# RF1_12V_RGBFlood.net
KiCad netlist of a schematic drawn in EAGLE
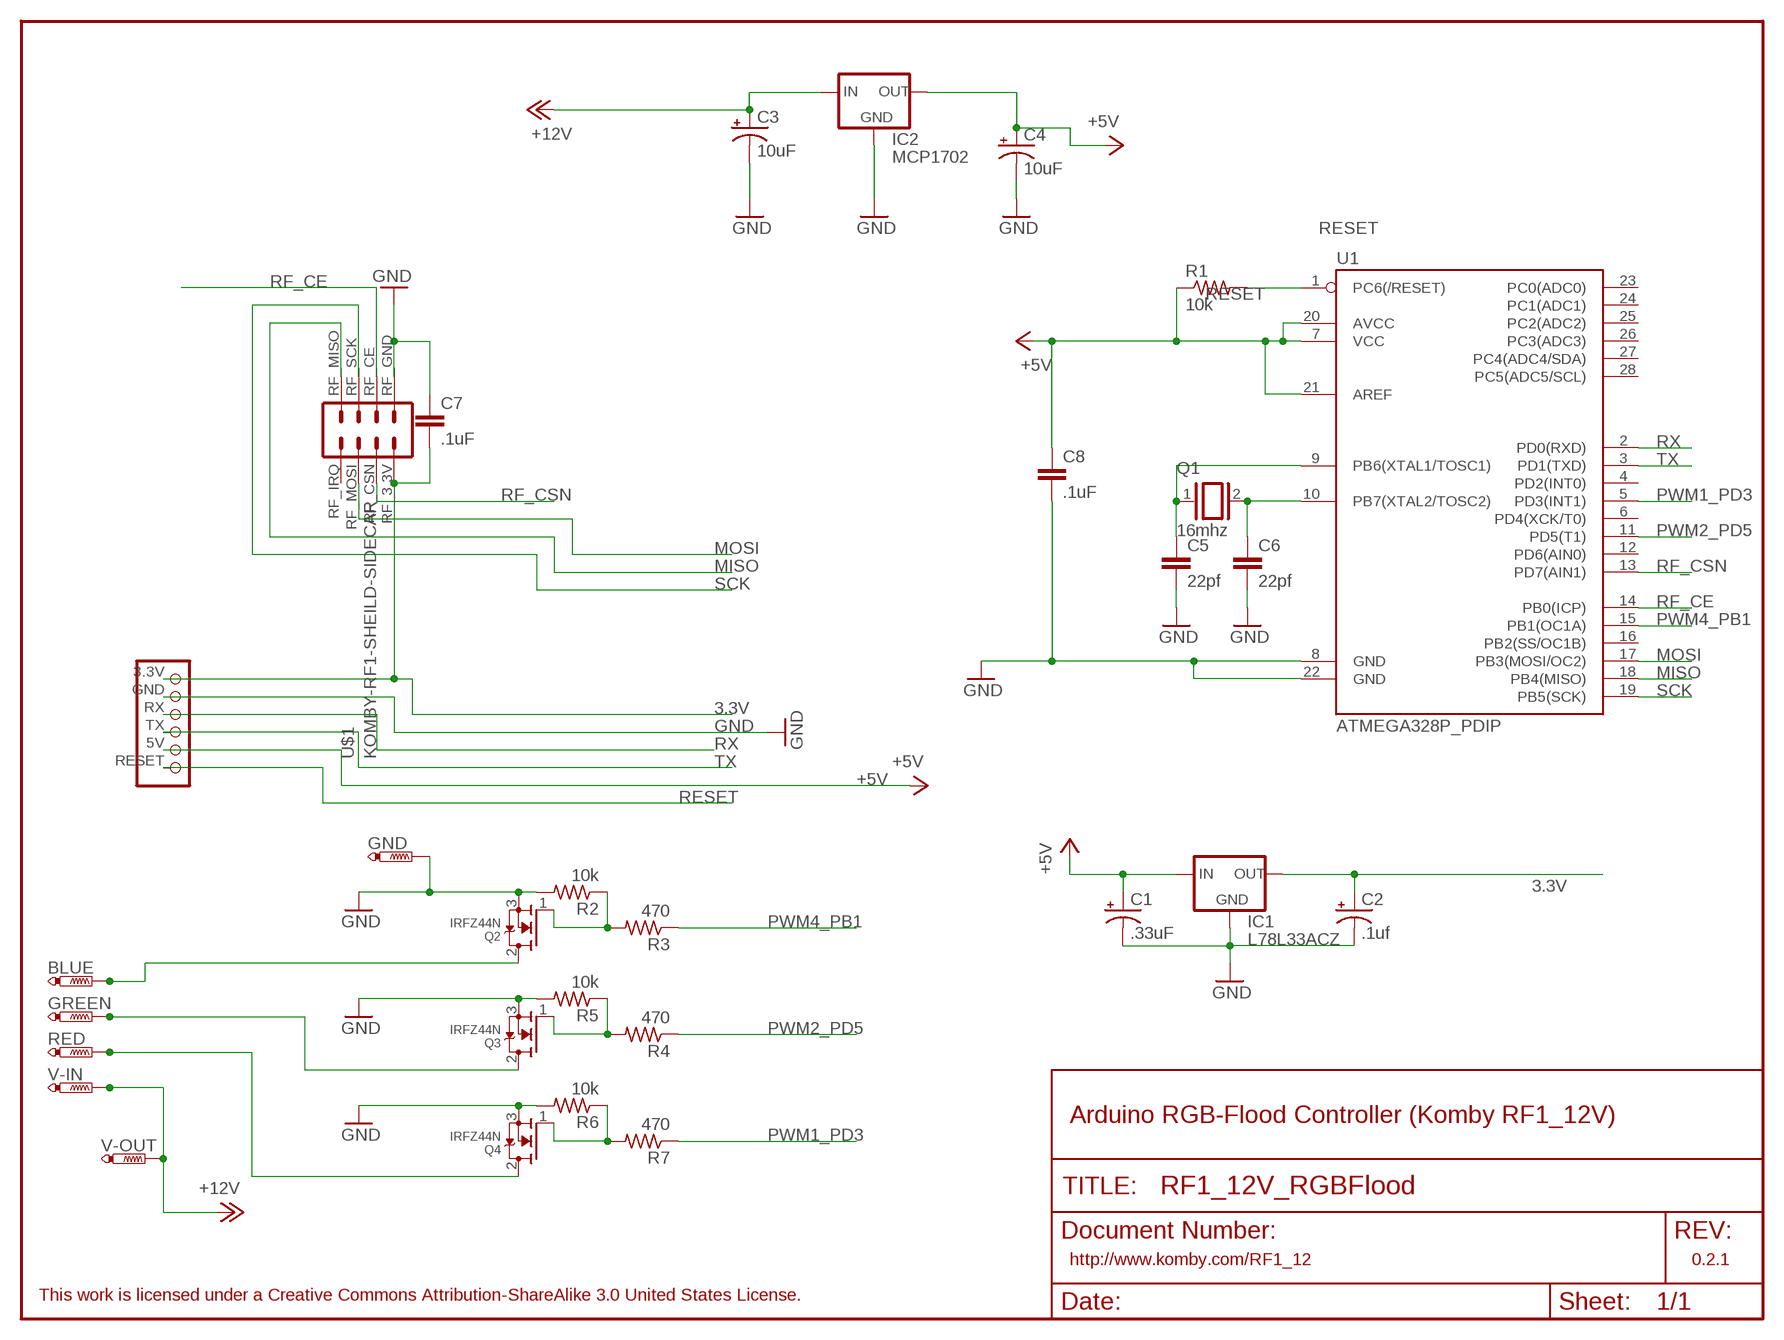
[diagram p0: schematic, sheet 1]

(export (version "E")
  (design (tool "Eeschema 10.0.6"))
  (components
    (comp (ref "BLUE")
      (value "PTR1PAD1-13Y")
      (footprint "eagle-import:P1-13Y")
      (libsource (lib "eagle-import") (part "PTR1PAD1-13Y"))
    )
    (comp (ref "C1")
      (value ".33uF")
      (footprint "eagle-import:E1,8-4")
      (libsource (lib "eagle-import") (part "CPOL-USE1.8-4"))
    )
    (comp (ref "C2")
      (value ".1uf")
      (footprint "eagle-import:E1,8-4")
      (libsource (lib "eagle-import") (part "CPOL-USE1.8-4"))
    )
    (comp (ref "C3")
      (value "10uF")
      (footprint "eagle-import:E1,8-4")
      (libsource (lib "eagle-import") (part "CPOL-USE1.8-4"))
    )
    (comp (ref "C4")
      (value "10uF")
      (footprint "eagle-import:E1,8-4")
      (libsource (lib "eagle-import") (part "CPOL-USE1.8-4"))
    )
    (comp (ref "C5")
      (value "22pf")
      (footprint "eagle-import:C025-024X044")
      (libsource (lib "eagle-import") (part "C-EU025-024X044"))
    )
    (comp (ref "C6")
      (value "22pf")
      (footprint "eagle-import:C025-024X044")
      (libsource (lib "eagle-import") (part "C-EU025-024X044"))
    )
    (comp (ref "C7")
      (value ".1uF")
      (footprint "eagle-import:C025-024X044")
      (libsource (lib "eagle-import") (part "C-EU025-024X044"))
    )
    (comp (ref "C8")
      (value ".1uF")
      (footprint "eagle-import:C025-024X044")
      (libsource (lib "eagle-import") (part "C-EU025-024X044"))
    )
    (comp (ref "GND")
      (value "PTR1PAD1-13Y")
      (footprint "eagle-import:P1-13Y")
      (libsource (lib "eagle-import") (part "PTR1PAD1-13Y"))
    )
    (comp (ref "GREEN")
      (value "PTR1PAD1-13Y")
      (footprint "eagle-import:P1-13Y")
      (libsource (lib "eagle-import") (part "PTR1PAD1-13Y"))
    )
    (comp (ref "IC1")
      (value "L78L33ACZ")
      (footprint "eagle-import:78LXX")
      (libsource (lib "eagle-import") (part "78LXX"))
    )
    (comp (ref "IC2")
      (value "MCP1702")
      (footprint "eagle-import:TO92")
      (libsource (lib "eagle-import") (part "MCP1700TRI"))
    )
    (comp (ref "Q1")
      (value "16mhz")
      (footprint "eagle-import:QS")
      (libsource (lib "eagle-import") (part "XTAL/S"))
    )
    (comp (ref "Q2")
      (value "IRFZ44N")
      (footprint "eagle-import:TO220V")
      (libsource (lib "eagle-import") (part "MOSFET-NGDS_TO220V"))
    )
    (comp (ref "Q3")
      (value "IRFZ44N")
      (footprint "eagle-import:TO220V")
      (libsource (lib "eagle-import") (part "MOSFET-NGDS_TO220V"))
    )
    (comp (ref "Q4")
      (value "IRFZ44N")
      (footprint "eagle-import:TO220V")
      (libsource (lib "eagle-import") (part "MOSFET-NGDS_TO220V"))
    )
    (comp (ref "R1")
      (value "10k")
      (footprint "eagle-import:0207_7")
      (libsource (lib "eagle-import") (part "R-US_0207/7"))
    )
    (comp (ref "R2")
      (value "10k")
      (footprint "eagle-import:0207_7")
      (libsource (lib "eagle-import") (part "adafruit_2_R-US_0207/7"))
    )
    (comp (ref "R3")
      (value "470")
      (footprint "eagle-import:0207_7")
      (libsource (lib "eagle-import") (part "adafruit_2_R-US_0207/7"))
    )
    (comp (ref "R4")
      (value "470")
      (footprint "eagle-import:0207_7")
      (libsource (lib "eagle-import") (part "adafruit_2_R-US_0207/7"))
    )
    (comp (ref "R5")
      (value "10k")
      (footprint "eagle-import:0207_7")
      (libsource (lib "eagle-import") (part "adafruit_2_R-US_0207/7"))
    )
    (comp (ref "R6")
      (value "10k")
      (footprint "eagle-import:0207_7")
      (libsource (lib "eagle-import") (part "adafruit_2_R-US_0207/7"))
    )
    (comp (ref "R7")
      (value "470")
      (footprint "eagle-import:0207_7")
      (libsource (lib "eagle-import") (part "adafruit_2_R-US_0207/7"))
    )
    (comp (ref "RED")
      (value "PTR1PAD1-13Y")
      (footprint "eagle-import:P1-13Y")
      (libsource (lib "eagle-import") (part "PTR1PAD1-13Y"))
    )
    (comp (ref "U$1")
      (value "KOMBY-RF1-SHEILD-SIDECAR")
      (footprint "eagle-import:KOMBY-RF1-SIDECAR")
      (libsource (lib "eagle-import") (part "KOMBY-RF1-SHEILD-SIDECAR"))
    )
    (comp (ref "U1")
      (value "ATMEGA328P_PDIP")
      (footprint "eagle-import:DIL28-3")
      (libsource (lib "eagle-import") (part "ATMEGA328P_PDIP"))
    )
    (comp (ref "V-IN")
      (value "PTR1PAD1-13Y")
      (footprint "eagle-import:P1-13Y")
      (libsource (lib "eagle-import") (part "PTR1PAD1-13Y"))
    )
    (comp (ref "V-OUT")
      (value "PTR1PAD1-13Y")
      (footprint "eagle-import:P1-13Y")
      (libsource (lib "eagle-import") (part "PTR1PAD1-13Y"))
    )
  )
  (nets
    (net (code "1") (name "+5V") (class "Default")
      (node (ref "C1") (pin "+") (pinfunction "+_+") (pintype "passive"))
      (node (ref "C4") (pin "+") (pinfunction "+_+") (pintype "passive"))
      (node (ref "C8") (pin "1") (pinfunction "1_1") (pintype "passive"))
      (node (ref "IC1") (pin "IN") (pinfunction "IN_IN") (pintype "input"))
      (node (ref "IC2") (pin "3") (pinfunction "OUT_3") (pintype "passive"))
      (node (ref "R1") (pin "1") (pinfunction "1_1") (pintype "passive"))
      (node (ref "U$1") (pin "5V") (pinfunction "5V_5V") (pintype "passive"))
      (node (ref "U1") (pin "20") (pinfunction "AVCC_20") (pintype "bidirectional"))
      (node (ref "U1") (pin "21") (pinfunction "AREF_21") (pintype "bidirectional"))
      (node (ref "U1") (pin "7") (pinfunction "VCC_7") (pintype "bidirectional"))
    )
    (net (code "2") (name "+12V") (class "Default")
      (node (ref "C3") (pin "+") (pinfunction "+_+") (pintype "passive"))
      (node (ref "IC2") (pin "2") (pinfunction "IN_2") (pintype "input"))
      (node (ref "V-IN") (pin "TP") (pinfunction "TP_TP") (pintype "input"))
      (node (ref "V-OUT") (pin "TP") (pinfunction "TP_TP") (pintype "input"))
    )
    (net (code "3") (name "/3.3V") (class "Default")
      (node (ref "C2") (pin "+") (pinfunction "+_+") (pintype "passive"))
      (node (ref "C7") (pin "2") (pinfunction "2_2") (pintype "passive"))
      (node (ref "IC1") (pin "OUT") (pinfunction "OUT_OUT") (pintype "passive"))
      (node (ref "U$1") (pin "3.3V") (pinfunction "3.3V_3.3V") (pintype "passive"))
      (node (ref "U$1") (pin "RF_3.3V") (pinfunction "RF_3.3V_RF_3.3V") (pintype "passive"))
    )
    (net (code "4") (name "/MISO") (class "Default")
      (node (ref "U$1") (pin "RF_MISO") (pinfunction "RF_MISO_RF_MISO") (pintype "passive"))
      (node (ref "U1") (pin "18") (pinfunction "PB4(MISO)_18") (pintype "bidirectional"))
    )
    (net (code "5") (name "/MOSI") (class "Default")
      (node (ref "U$1") (pin "RF_MOSI") (pinfunction "RF_MOSI_RF_MOSI") (pintype "passive"))
      (node (ref "U1") (pin "17") (pinfunction "PB3(MOSI/OC2)_17") (pintype "bidirectional"))
    )
    (net (code "6") (name "/PWM1_PD3") (class "Default")
      (node (ref "R7") (pin "1") (pinfunction "1_1") (pintype "passive"))
      (node (ref "U1") (pin "5") (pinfunction "PD3(INT1)_5") (pintype "bidirectional"))
    )
    (net (code "7") (name "/PWM2_PD5") (class "Default")
      (node (ref "R4") (pin "1") (pinfunction "1_1") (pintype "passive"))
      (node (ref "U1") (pin "11") (pinfunction "PD5(T1)_11") (pintype "bidirectional"))
    )
    (net (code "8") (name "/PWM4_PB1") (class "Default")
      (node (ref "R3") (pin "1") (pinfunction "1_1") (pintype "passive"))
      (node (ref "U1") (pin "15") (pinfunction "PB1(OC1A)_15") (pintype "bidirectional"))
    )
    (net (code "9") (name "/RESET") (class "Default")
      (node (ref "R1") (pin "2") (pinfunction "2_2") (pintype "passive"))
      (node (ref "U$1") (pin "RESET") (pinfunction "RESET_RESET") (pintype "passive"))
      (node (ref "U1") (pin "1") (pinfunction "PC6(/RESET)_1") (pintype "bidirectional"))
    )
    (net (code "10") (name "/RF_CE") (class "Default")
      (node (ref "U$1") (pin "RF_CE") (pinfunction "RF_CE_RF_CE") (pintype "passive"))
      (node (ref "U1") (pin "14") (pinfunction "PB0(ICP)_14") (pintype "bidirectional"))
    )
    (net (code "11") (name "/RF_CSN") (class "Default")
      (node (ref "U$1") (pin "RF_CSN") (pinfunction "RF_CSN_RF_CSN") (pintype "passive"))
      (node (ref "U1") (pin "13") (pinfunction "PD7(AIN1)_13") (pintype "bidirectional"))
    )
    (net (code "12") (name "/RX") (class "Default")
      (node (ref "U$1") (pin "RX") (pinfunction "RX_RX") (pintype "passive"))
      (node (ref "U1") (pin "2") (pinfunction "PD0(RXD)_2") (pintype "bidirectional"))
    )
    (net (code "13") (name "/SCK") (class "Default")
      (node (ref "U$1") (pin "RF_SCK") (pinfunction "RF_SCK_RF_SCK") (pintype "passive"))
      (node (ref "U1") (pin "19") (pinfunction "PB5(SCK)_19") (pintype "bidirectional"))
    )
    (net (code "14") (name "/TX") (class "Default")
      (node (ref "U$1") (pin "TX") (pinfunction "TX_TX") (pintype "passive"))
      (node (ref "U1") (pin "3") (pinfunction "PD1(TXD)_3") (pintype "bidirectional"))
    )
    (net (code "15") (name "GND") (class "Default")
      (node (ref "C1") (pin "-") (pinfunction "-_-") (pintype "passive"))
      (node (ref "C2") (pin "-") (pinfunction "-_-") (pintype "passive"))
      (node (ref "C3") (pin "-") (pinfunction "-_-") (pintype "passive"))
      (node (ref "C4") (pin "-") (pinfunction "-_-") (pintype "passive"))
      (node (ref "C5") (pin "2") (pinfunction "2_2") (pintype "passive"))
      (node (ref "C6") (pin "2") (pinfunction "2_2") (pintype "passive"))
      (node (ref "C7") (pin "1") (pinfunction "1_1") (pintype "passive"))
      (node (ref "C8") (pin "2") (pinfunction "2_2") (pintype "passive"))
      (node (ref "GND") (pin "TP") (pinfunction "TP_TP") (pintype "input"))
      (node (ref "IC1") (pin "GND") (pinfunction "GND_GND") (pintype "input"))
      (node (ref "IC2") (pin "1") (pinfunction "GND_1") (pintype "input"))
      (node (ref "Q2") (pin "3") (pinfunction "S_3") (pintype "bidirectional"))
      (node (ref "Q3") (pin "3") (pinfunction "S_3") (pintype "bidirectional"))
      (node (ref "Q4") (pin "3") (pinfunction "S_3") (pintype "bidirectional"))
      (node (ref "R2") (pin "2") (pinfunction "2_2") (pintype "passive"))
      (node (ref "R5") (pin "2") (pinfunction "2_2") (pintype "passive"))
      (node (ref "R6") (pin "2") (pinfunction "2_2") (pintype "passive"))
      (node (ref "U$1") (pin "GND") (pinfunction "GND_GND") (pintype "passive"))
      (node (ref "U$1") (pin "RF_GND") (pinfunction "RFGND_1_RF_GND") (pintype "passive"))
      (node (ref "U1") (pin "22") (pinfunction "GND_22") (pintype "bidirectional"))
      (node (ref "U1") (pin "8") (pinfunction "GND_8") (pintype "bidirectional"))
    )
    (net (code "16") (name "Net-(Q2-D)") (class "Default")
      (node (ref "BLUE") (pin "TP") (pinfunction "TP_TP") (pintype "input"))
      (node (ref "Q2") (pin "2") (pinfunction "D_2") (pintype "bidirectional"))
    )
    (net (code "17") (name "Net-(Q2-G)") (class "Default")
      (node (ref "Q2") (pin "1") (pinfunction "G_1") (pintype "bidirectional"))
      (node (ref "R2") (pin "1") (pinfunction "1_1") (pintype "passive"))
      (node (ref "R3") (pin "2") (pinfunction "2_2") (pintype "passive"))
    )
    (net (code "18") (name "Net-(Q3-D)") (class "Default")
      (node (ref "GREEN") (pin "TP") (pinfunction "TP_TP") (pintype "input"))
      (node (ref "Q3") (pin "2") (pinfunction "D_2") (pintype "bidirectional"))
    )
    (net (code "19") (name "Net-(Q3-G)") (class "Default")
      (node (ref "Q3") (pin "1") (pinfunction "G_1") (pintype "bidirectional"))
      (node (ref "R4") (pin "2") (pinfunction "2_2") (pintype "passive"))
      (node (ref "R5") (pin "1") (pinfunction "1_1") (pintype "passive"))
    )
    (net (code "20") (name "Net-(Q4-D)") (class "Default")
      (node (ref "Q4") (pin "2") (pinfunction "D_2") (pintype "bidirectional"))
      (node (ref "RED") (pin "TP") (pinfunction "TP_TP") (pintype "input"))
    )
    (net (code "21") (name "Net-(Q4-G)") (class "Default")
      (node (ref "Q4") (pin "1") (pinfunction "G_1") (pintype "bidirectional"))
      (node (ref "R6") (pin "1") (pinfunction "1_1") (pintype "passive"))
      (node (ref "R7") (pin "2") (pinfunction "2_2") (pintype "passive"))
    )
    (net (code "22") (name "Net-(U1-PB6(XTAL1{slash}TOSC1))") (class "Default")
      (node (ref "C5") (pin "1") (pinfunction "1_1") (pintype "passive"))
      (node (ref "Q1") (pin "1") (pinfunction "1_1") (pintype "passive"))
      (node (ref "U1") (pin "9") (pinfunction "PB6(XTAL1/TOSC1)_9") (pintype "bidirectional"))
    )
    (net (code "23") (name "Net-(U1-PB7(XTAL2{slash}TOSC2))") (class "Default")
      (node (ref "C6") (pin "1") (pinfunction "1_1") (pintype "passive"))
      (node (ref "Q1") (pin "2") (pinfunction "2_2") (pintype "passive"))
      (node (ref "U1") (pin "10") (pinfunction "PB7(XTAL2/TOSC2)_10") (pintype "bidirectional"))
    )
    (net (code "24") (name "unconnected-(U$1-PadRF_IRQ)") (class "Default")
      (node (ref "U$1") (pin "RF_IRQ") (pinfunction "RF_IRQ_RF_IRQ") (pintype "passive"))
    )
    (net (code "25") (name "unconnected-(U1-PB2(SS{slash}OC1B)-Pad16)") (class "Default")
      (node (ref "U1") (pin "16") (pinfunction "PB2(SS/OC1B)_16") (pintype "bidirectional"))
    )
    (net (code "26") (name "unconnected-(U1-PC0(ADC0)-Pad23)") (class "Default")
      (node (ref "U1") (pin "23") (pinfunction "PC0(ADC0)_23") (pintype "bidirectional"))
    )
    (net (code "27") (name "unconnected-(U1-PC1(ADC1)-Pad24)") (class "Default")
      (node (ref "U1") (pin "24") (pinfunction "PC1(ADC1)_24") (pintype "bidirectional"))
    )
    (net (code "28") (name "unconnected-(U1-PC2(ADC2)-Pad25)") (class "Default")
      (node (ref "U1") (pin "25") (pinfunction "PC2(ADC2)_25") (pintype "bidirectional"))
    )
    (net (code "29") (name "unconnected-(U1-PC3(ADC3)-Pad26)") (class "Default")
      (node (ref "U1") (pin "26") (pinfunction "PC3(ADC3)_26") (pintype "bidirectional"))
    )
    (net (code "30") (name "unconnected-(U1-PC4(ADC4{slash}SDA)-Pad27)") (class "Default")
      (node (ref "U1") (pin "27") (pinfunction "PC4(ADC4/SDA)_27") (pintype "bidirectional"))
    )
    (net (code "31") (name "unconnected-(U1-PC5(ADC5{slash}SCL)-Pad28)") (class "Default")
      (node (ref "U1") (pin "28") (pinfunction "PC5(ADC5/SCL)_28") (pintype "bidirectional"))
    )
    (net (code "32") (name "unconnected-(U1-PD2(INT0)-Pad4)") (class "Default")
      (node (ref "U1") (pin "4") (pinfunction "PD2(INT0)_4") (pintype "bidirectional"))
    )
    (net (code "33") (name "unconnected-(U1-PD4(XCK{slash}T0)-Pad6)") (class "Default")
      (node (ref "U1") (pin "6") (pinfunction "PD4(XCK/T0)_6") (pintype "bidirectional"))
    )
    (net (code "34") (name "unconnected-(U1-PD6(AIN0)-Pad12)") (class "Default")
      (node (ref "U1") (pin "12") (pinfunction "PD6(AIN0)_12") (pintype "bidirectional"))
    )
  )
)
